# transmitter_SCH.net
KiCad netlist of a schematic drawn in Altium Designer
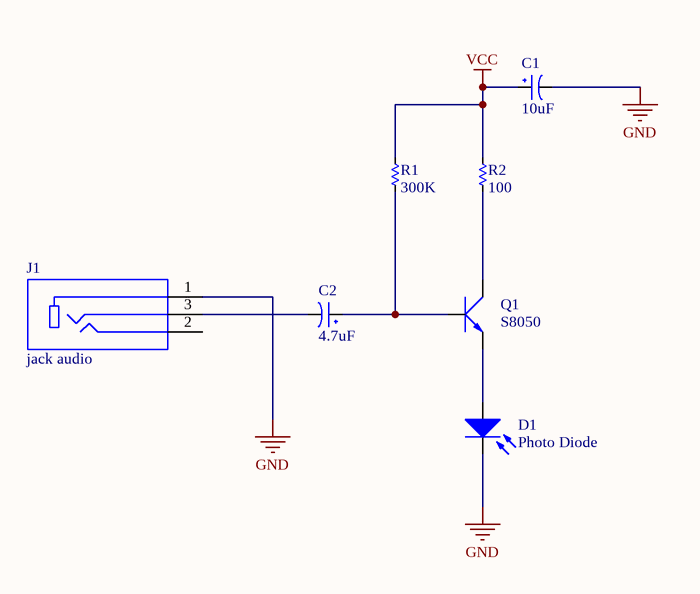
[diagram p0: transmitter_SCH.SchDoc]

(export (version "E")
  (design (tool "Eeschema 10.0.6"))
  (components
    (comp (ref "C1")
      (value "10uF")
      (footprint "tu hoa 4mm")
      (description "Cắm")
      (libsource (lib "THU VIEN SCH") (part "Tu Hoa 10uF 16V 4x7"))
    )
    (comp (ref "C2")
      (value "4.7uF")
      (footprint "tu hoa 5mm")
      (description "Cắm")
      (libsource (lib "THU VIEN SCH") (part "Tu Hoa 4.7uF 50V 5x11"))
    )
    (comp (ref "D1")
      (value "Photo Diode")
      (footprint "LED-5 GRe")
      (description "Photosensitive Diode")
      (libsource (lib "Compiled_Devzone") (part "Photo Diode"))
    )
    (comp (ref "J1")
      (value "jack audio")
      (footprint "CUI_SJ1-3533N")
      (libsource (lib "private_SCH") (part "jack audio"))
    )
    (comp (ref "Q1")
      (value "S8050")
      (footprint "TO92-123")
      (description "NPN 600mW, ECB")
      (libsource (lib "TechMT.VN_Lib_Project v2") (part "2N904"))
    )
    (comp (ref "R1")
      (value "300K")
      (footprint "RES-2W")
      (description "Res")
      (fields
        (field (name "MANUFACTURER") "Generic Components")
        (field (name "PUBLISHER") "Altium Hobart Technology Centre")
      )
      (libsource (lib "TechMT.VN_Lib_Project v2") (part "Res"))
    )
    (comp (ref "R2")
      (value "100")
      (footprint "RES-2W")
      (description "Res")
      (fields
        (field (name "MANUFACTURER") "Generic Components")
        (field (name "PUBLISHER") "Altium Hobart Technology Centre")
      )
      (libsource (lib "TechMT.VN_Lib_Project v2") (part "Res"))
    )
  )
  (nets
    (net (code "1") (name "GND") (class "Default")
      (node (ref "C1") (pin "2") (pinfunction "2_2") (pintype "passive"))
      (node (ref "D1") (pin "2") (pinfunction "K_2") (pintype "passive"))
      (node (ref "J1") (pin "1") (pinfunction "1_1") (pintype "passive"))
    )
    (net (code "2") (name "Net-(C2-Pad2)") (class "Default")
      (node (ref "C2") (pin "2") (pinfunction "2_2") (pintype "passive"))
      (node (ref "J1") (pin "3") (pinfunction "3_3") (pintype "passive"))
    )
    (net (code "3") (name "Net-(D1-A)") (class "Default")
      (node (ref "D1") (pin "1") (pinfunction "A_1") (pintype "passive"))
      (node (ref "Q1") (pin "1") (pinfunction "E_1") (pintype "passive"))
    )
    (net (code "4") (name "Net-(Q1-B)") (class "Default")
      (node (ref "C2") (pin "1") (pinfunction "1_1") (pintype "passive"))
      (node (ref "Q1") (pin "2") (pinfunction "B_2") (pintype "passive"))
      (node (ref "R1") (pin "2") (pinfunction "2_2") (pintype "passive"))
    )
    (net (code "5") (name "Net-(Q1-C)") (class "Default")
      (node (ref "Q1") (pin "3") (pinfunction "C_3") (pintype "passive"))
      (node (ref "R2") (pin "2") (pinfunction "2_2") (pintype "passive"))
    )
    (net (code "6") (name "VCC") (class "Default")
      (node (ref "C1") (pin "1") (pinfunction "1_1") (pintype "passive"))
      (node (ref "R1") (pin "1") (pinfunction "1_1") (pintype "passive"))
      (node (ref "R2") (pin "1") (pinfunction "1_1") (pintype "passive"))
    )
    (net (code "7") (name "unconnected-(J1-Pad2)") (class "Default")
      (node (ref "J1") (pin "2") (pinfunction "2_2") (pintype "passive"))
    )
  )
)
